# 2_MCU.net
KiCad netlist of a schematic drawn in Altium Designer
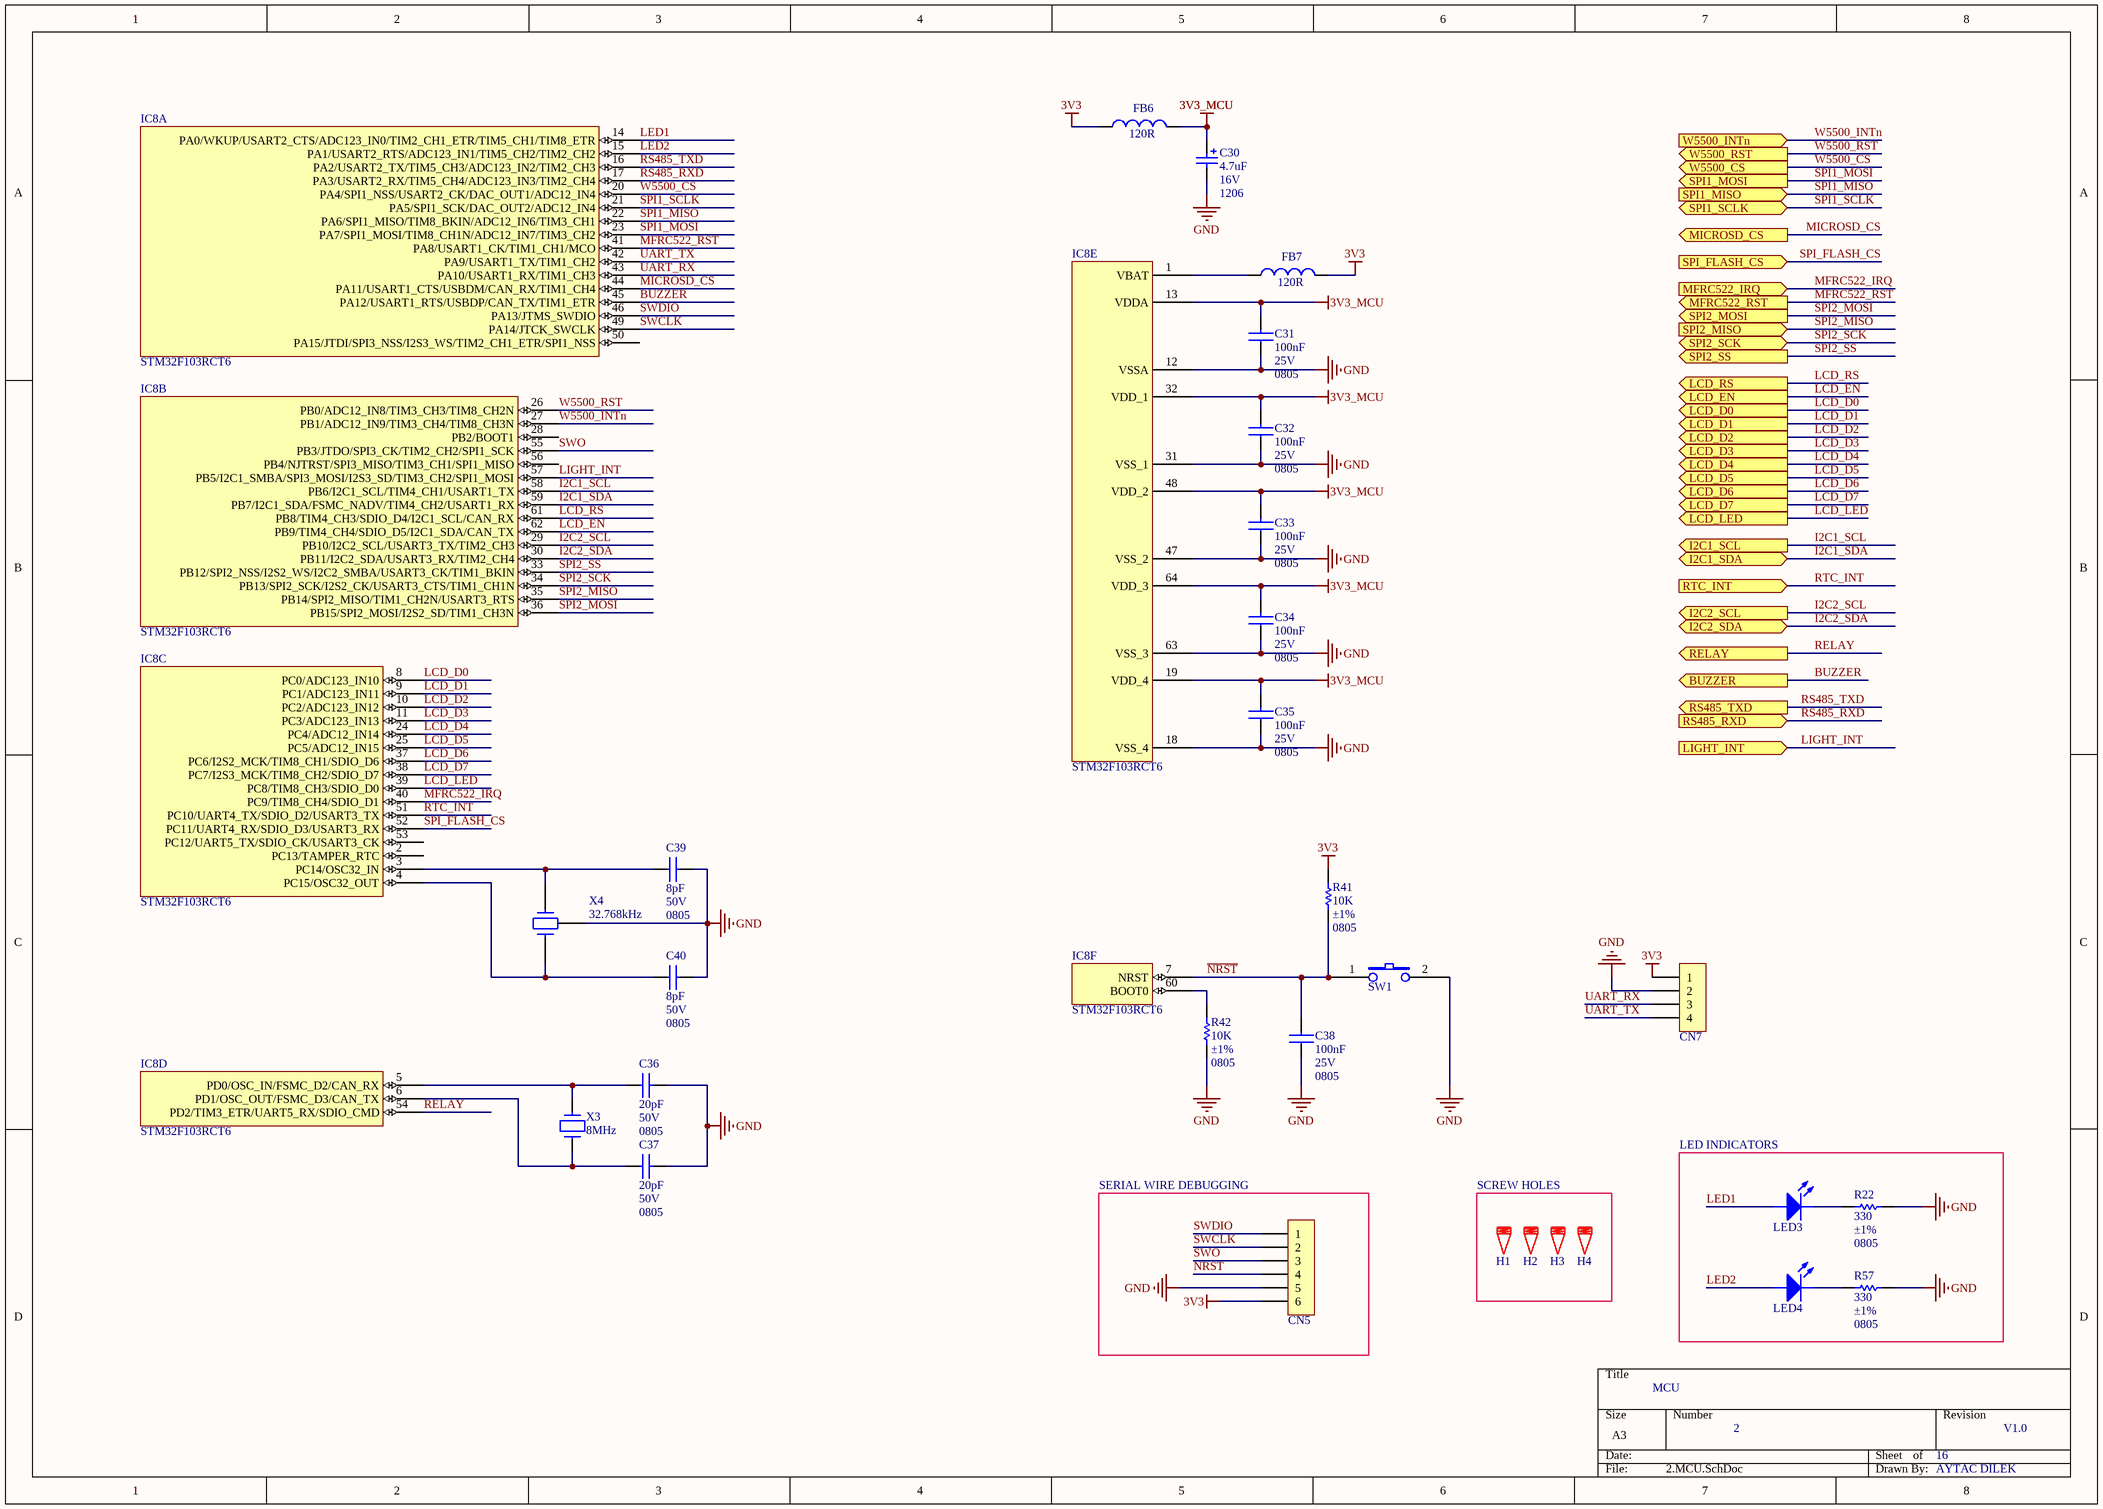
[diagram p0: 2.MCU.SchDoc]

(export (version "E")
  (design (tool "Eeschema 10.0.6"))
  (components
    (comp (ref "C30")
      (value "4.7uF")
      (footprint "CAPMP3216X16N_EIA-1206_CASE-A")
      (description "CAP TANT 4.7UF 16V 10% 1206")
      (fields
        (field (name "PART NUMBER") "SCAP01400003")
        (field (name "TOLERANCE") "±10%")
        (field (name "VOLTAGE - RATED") "16V")
        (field (name "PACKAGE / CASE") "1206")
      )
      (libsource (lib "ComponentDatabase") (part "CAP_P"))
    )
    (comp (ref "C31")
      (value "CAP_NP")
      (footprint "CAPC2012X100N_EIA0805")
      (description "CAP CER 0.1UF 25V X7R 0805")
      (fields
        (field (name "PART NUMBER") "SCAP00300093")
        (field (name "CAPACITANCE") "100nF")
        (field (name "TOLERANCE") "±10%")
        (field (name "VOLTAGE - RATED") "25V")
        (field (name "PACKAGE / CASE") "0805")
      )
      (libsource (lib "ComponentDatabase") (part "CAP_NP"))
    )
    (comp (ref "C32")
      (value "CAP_NP")
      (footprint "CAPC2012X100N_EIA0805")
      (description "CAP CER 0.1UF 25V X7R 0805")
      (fields
        (field (name "PART NUMBER") "SCAP00300093")
        (field (name "CAPACITANCE") "100nF")
        (field (name "TOLERANCE") "±10%")
        (field (name "VOLTAGE - RATED") "25V")
        (field (name "PACKAGE / CASE") "0805")
      )
      (libsource (lib "ComponentDatabase") (part "CAP_NP"))
    )
    (comp (ref "C33")
      (value "CAP_NP")
      (footprint "CAPC2012X100N_EIA0805")
      (description "CAP CER 0.1UF 25V X7R 0805")
      (fields
        (field (name "PART NUMBER") "SCAP00300093")
        (field (name "CAPACITANCE") "100nF")
        (field (name "TOLERANCE") "±10%")
        (field (name "VOLTAGE - RATED") "25V")
        (field (name "PACKAGE / CASE") "0805")
      )
      (libsource (lib "ComponentDatabase") (part "CAP_NP"))
    )
    (comp (ref "C34")
      (value "CAP_NP")
      (footprint "CAPC2012X100N_EIA0805")
      (description "CAP CER 0.1UF 25V X7R 0805")
      (fields
        (field (name "PART NUMBER") "SCAP00300093")
        (field (name "CAPACITANCE") "100nF")
        (field (name "TOLERANCE") "±10%")
        (field (name "VOLTAGE - RATED") "25V")
        (field (name "PACKAGE / CASE") "0805")
      )
      (libsource (lib "ComponentDatabase") (part "CAP_NP"))
    )
    (comp (ref "C35")
      (value "CAP_NP")
      (footprint "CAPC2012X100N_EIA0805")
      (description "CAP CER 0.1UF 25V X7R 0805")
      (fields
        (field (name "PART NUMBER") "SCAP00300093")
        (field (name "CAPACITANCE") "100nF")
        (field (name "TOLERANCE") "±10%")
        (field (name "VOLTAGE - RATED") "25V")
        (field (name "PACKAGE / CASE") "0805")
      )
      (libsource (lib "ComponentDatabase") (part "CAP_NP"))
    )
    (comp (ref "C36")
      (value "CAP_NP")
      (footprint "CAPC2012X100N_EIA0805")
      (description "CAP CER 20PF 50V NP0 0805")
      (fields
        (field (name "PART NUMBER") "SCAP00300041")
        (field (name "CAPACITANCE") "20pF")
        (field (name "TOLERANCE") "±5%")
        (field (name "VOLTAGE - RATED") "50V")
        (field (name "PACKAGE / CASE") "0805")
      )
      (libsource (lib "ComponentDatabase") (part "CAP_NP"))
    )
    (comp (ref "C37")
      (value "CAP_NP")
      (footprint "CAPC2012X100N_EIA0805")
      (description "CAP CER 20PF 50V NP0 0805")
      (fields
        (field (name "PART NUMBER") "SCAP00300041")
        (field (name "CAPACITANCE") "20pF")
        (field (name "TOLERANCE") "±5%")
        (field (name "VOLTAGE - RATED") "50V")
        (field (name "PACKAGE / CASE") "0805")
      )
      (libsource (lib "ComponentDatabase") (part "CAP_NP"))
    )
    (comp (ref "C38")
      (value "CAP_NP")
      (footprint "CAPC2012X100N_EIA0805")
      (description "CAP CER 0.1UF 25V X7R 0805")
      (fields
        (field (name "PART NUMBER") "SCAP00300093")
        (field (name "CAPACITANCE") "100nF")
        (field (name "TOLERANCE") "±10%")
        (field (name "VOLTAGE - RATED") "25V")
        (field (name "PACKAGE / CASE") "0805")
      )
      (libsource (lib "ComponentDatabase") (part "CAP_NP"))
    )
    (comp (ref "C39")
      (value "CAP_NP")
      (footprint "CAPC2012X100N_EIA0805")
      (description "CAP CER 8PF 50V NP0 0805")
      (fields
        (field (name "PART NUMBER") "SCAP00300030")
        (field (name "CAPACITANCE") "8pF")
        (field (name "TOLERANCE") "±0.25pF")
        (field (name "VOLTAGE - RATED") "50V")
        (field (name "PACKAGE / CASE") "0805")
      )
      (libsource (lib "ComponentDatabase") (part "CAP_NP"))
    )
    (comp (ref "C40")
      (value "CAP_NP")
      (footprint "CAPC2012X100N_EIA0805")
      (description "CAP CER 8PF 50V NP0 0805")
      (fields
        (field (name "PART NUMBER") "SCAP00300030")
        (field (name "CAPACITANCE") "8pF")
        (field (name "TOLERANCE") "±0.25pF")
        (field (name "VOLTAGE - RATED") "50V")
        (field (name "PACKAGE / CASE") "0805")
      )
      (libsource (lib "ComponentDatabase") (part "CAP_NP"))
    )
    (comp (ref "CN5")
      (value "HDR_1X6")
      (footprint "HDRFV6W70P254_1X6_1524X254X1118P")
      (description "CONN ARDUINO HEADER .0100\" 6POS")
      (fields (field (name "PART NUMBER") "SCON00124") (field (name "MANUFACTURER") "Sparkfun"))
      (libsource (lib "ComponentDatabase") (part "HDR_1X6"))
    )
    (comp (ref "CN7")
      (value "HDR_1X4")
      (footprint "HDRFV4W70P254_1X4_1016X254X1118P")
      (description "CONN HEADER 4 POS 2.54")
      (fields (field (name "PART NUMBER") "SCON00140") (field (name "MANUFACTURER") "Wurth Electronics Inc"))
      (libsource (lib "ComponentDatabase") (part "HDR_1X4"))
    )
    (comp (ref "FB6")
      (value "BEAD")
      (footprint "FILC2012X100N_EIA0805")
      (description "FERRITE CHIP POWER 120 OHM SMD")
      (fields
        (field (name "PART NUMBER") "SFIL00005")
        (field (name "IMPEDANCE") "120R")
        (field (name "MANUFACTURER") "Laird-Signal Integrity Products")
      )
      (libsource (lib "ComponentDatabase") (part "BEAD"))
    )
    (comp (ref "FB7")
      (value "BEAD")
      (footprint "FILC2012X100N_EIA0805")
      (description "FERRITE CHIP POWER 120 OHM SMD")
      (fields
        (field (name "PART NUMBER") "SFIL00005")
        (field (name "IMPEDANCE") "120R")
        (field (name "MANUFACTURER") "Laird-Signal Integrity Products")
      )
      (libsource (lib "ComponentDatabase") (part "BEAD"))
    )
    (comp (ref "H1")
      (value "HOLES")
      (footprint "HOLE_125MIL")
      (description "Holes")
      (fields (field (name "PART NUMBER") "SMSC00005"))
      (libsource (lib "ComponentDatabase") (part "HOLES"))
    )
    (comp (ref "H2")
      (value "HOLES")
      (footprint "HOLE_125MIL")
      (description "Holes")
      (fields (field (name "PART NUMBER") "SMSC00005"))
      (libsource (lib "ComponentDatabase") (part "HOLES"))
    )
    (comp (ref "H3")
      (value "HOLES")
      (footprint "HOLE_125MIL")
      (description "Holes")
      (fields (field (name "PART NUMBER") "SMSC00005"))
      (libsource (lib "ComponentDatabase") (part "HOLES"))
    )
    (comp (ref "H4")
      (value "HOLES")
      (footprint "HOLE_125MIL")
      (description "Holes")
      (fields (field (name "PART NUMBER") "SMSC00005"))
      (libsource (lib "ComponentDatabase") (part "HOLES"))
    )
    (comp (ref "IC8")
      (value "STM32F103RCT6")
      (footprint "QFP50P1200X1200X160-64N")
      (description "IC MCU 32BIT 256KB FLASH 64LQFP")
      (fields
        (field (name "PART NUMBER") "SIC00045")
        (field (name "MANUFACTURER PART NUMBER") "STM32F103RCT6")
        (field (name "MANUFACTURER") "STMicroelectronics")
      )
      (libsource (lib "ComponentDatabase") (part "STM32F103RCT6"))
    )
    (comp (ref "LED3")
      (value "LED")
      (footprint "LEDC2012X70N_EIA0805_RED")
      (description "LED SUPER RED CLR THIN 0805 SMD")
      (fields (field (name "PART NUMBER") "SOPT00004") (field (name "MANUFACTURER") "Lite-On Inc"))
      (libsource (lib "ComponentDatabase") (part "LED"))
    )
    (comp (ref "LED4")
      (value "LED")
      (footprint "LEDC2012X70N_EIA0805_RED")
      (description "LED SUPER RED CLR THIN 0805 SMD")
      (fields (field (name "PART NUMBER") "SOPT00004") (field (name "MANUFACTURER") "Lite-On Inc"))
      (libsource (lib "ComponentDatabase") (part "LED"))
    )
    (comp (ref "R22")
      (value "RES")
      (footprint "RESC2013X65N_EIA0805")
      (description "RES SMD 330 OHM 1% 1/8W 0805")
      (fields
        (field (name "PART NUMBER") "SRES03010062")
        (field (name "RESISTANCE (OHM)") "330")
        (field (name "TOLERANCE") "±1%")
        (field (name "PACKAGE / CASE") "0805")
        (field (name "MANUFACTURER") "Yageo")
      )
      (libsource (lib "ComponentDatabase") (part "RES"))
    )
    (comp (ref "R41")
      (value "RES")
      (footprint "RESC2013X65N_EIA0805")
      (description "RES SMD 10K OHM 1% 1/8W 0805")
      (fields
        (field (name "PART NUMBER") "SRES03010098")
        (field (name "RESISTANCE (OHM)") "10K")
        (field (name "TOLERANCE") "±1%")
        (field (name "PACKAGE / CASE") "0805")
        (field (name "MANUFACTURER") "Yageo")
      )
      (libsource (lib "ComponentDatabase") (part "RES"))
    )
    (comp (ref "R42")
      (value "RES")
      (footprint "RESC2013X65N_EIA0805")
      (description "RES SMD 10K OHM 1% 1/8W 0805")
      (fields
        (field (name "PART NUMBER") "SRES03010098")
        (field (name "RESISTANCE (OHM)") "10K")
        (field (name "TOLERANCE") "±1%")
        (field (name "PACKAGE / CASE") "0805")
        (field (name "MANUFACTURER") "Yageo")
      )
      (libsource (lib "ComponentDatabase") (part "RES"))
    )
    (comp (ref "R57")
      (value "RES")
      (footprint "RESC2013X65N_EIA0805")
      (description "RES SMD 330 OHM 1% 1/8W 0805")
      (fields
        (field (name "PART NUMBER") "SRES03010062")
        (field (name "RESISTANCE (OHM)") "330")
        (field (name "TOLERANCE") "±1%")
        (field (name "PACKAGE / CASE") "0805")
        (field (name "MANUFACTURER") "Yageo")
      )
      (libsource (lib "ComponentDatabase") (part "RES"))
    )
    (comp (ref "SW1")
      (value "SWITCH_TACTILE_2PIN")
      (footprint "[C&K]RS-282G05A3-SM_RT")
      (description "SWITCH TACTILE SPST-NO 0.05A 12V")
      (fields (field (name "PART NUMBER") "SSWI00022") (field (name "VOLTAGE") "12VDC"))
      (libsource (lib "ComponentDatabase") (part "SWITCH_TACTILE_2PIN"))
    )
    (comp (ref "X3")
      (value "8MHz")
      (footprint "HC-49/US")
      (description "CRYSTAL 8.0000MHZ 20PF T/H")
      (fields (field (name "PART NUMBER") "SCRY00001") (field (name "MANUFACTURER") "CTS-Frequency Controls"))
      (libsource (lib "ComponentDatabase") (part "CRYSTAL"))
    )
    (comp (ref "X4")
      (value "32.768kHz")
      (footprint "32.768_DIP")
      (description "CRYSTAL 32.768KHZ 6PF THRU")
      (fields (field (name "PART NUMBER") "SCRY00009") (field (name "MANUFACTURER") "Seiko Instruments"))
      (libsource (lib "ComponentDatabase") (part "CRYSTAL_32K"))
    )
  )
  (nets
    (net (code "1") (name "/BUZZER") (class "Default")
      (node (ref "IC8") (pin "45") (pinfunction "PA12/USART1_RTS/USBDP/CAN_TX/TIM1_ETR_45") (pintype "bidirectional"))
    )
    (net (code "2") (name "/I2C1_SCL") (class "Default")
      (node (ref "IC8") (pin "58") (pinfunction "PB6/I2C1_SCL/TIM4_CH1/USART1_TX_58") (pintype "bidirectional"))
    )
    (net (code "3") (name "/I2C1_SDA") (class "Default")
      (node (ref "IC8") (pin "59") (pinfunction "PB7/I2C1_SDA/FSMC_NADV/TIM4_CH2/USART1_RX_59") (pintype "bidirectional"))
    )
    (net (code "4") (name "/I2C2_SCL") (class "Default")
      (node (ref "IC8") (pin "29") (pinfunction "PB10/I2C2_SCL/USART3_TX/TIM2_CH3_29") (pintype "bidirectional"))
    )
    (net (code "5") (name "/I2C2_SDA") (class "Default")
      (node (ref "IC8") (pin "30") (pinfunction "PB11/I2C2_SDA/USART3_RX/TIM2_CH4_30") (pintype "bidirectional"))
    )
    (net (code "6") (name "/LCD_D0") (class "Default")
      (node (ref "IC8") (pin "8") (pinfunction "PC0/ADC123_IN10_8") (pintype "bidirectional"))
    )
    (net (code "7") (name "/LCD_D1") (class "Default")
      (node (ref "IC8") (pin "9") (pinfunction "PC1/ADC123_IN11_9") (pintype "bidirectional"))
    )
    (net (code "8") (name "/LCD_D2") (class "Default")
      (node (ref "IC8") (pin "10") (pinfunction "PC2/ADC123_IN12_10") (pintype "bidirectional"))
    )
    (net (code "9") (name "/LCD_D3") (class "Default")
      (node (ref "IC8") (pin "11") (pinfunction "PC3/ADC123_IN13_11") (pintype "bidirectional"))
    )
    (net (code "10") (name "/LCD_D4") (class "Default")
      (node (ref "IC8") (pin "24") (pinfunction "PC4/ADC12_IN14_24") (pintype "bidirectional"))
    )
    (net (code "11") (name "/LCD_D5") (class "Default")
      (node (ref "IC8") (pin "25") (pinfunction "PC5/ADC12_IN15_25") (pintype "bidirectional"))
    )
    (net (code "12") (name "/LCD_D6") (class "Default")
      (node (ref "IC8") (pin "37") (pinfunction "PC6/I2S2_MCK/TIM8_CH1/SDIO_D6_37") (pintype "bidirectional"))
    )
    (net (code "13") (name "/LCD_D7") (class "Default")
      (node (ref "IC8") (pin "38") (pinfunction "PC7/I2S3_MCK/TIM8_CH2/SDIO_D7_38") (pintype "bidirectional"))
    )
    (net (code "14") (name "/LCD_EN") (class "Default")
      (node (ref "IC8") (pin "62") (pinfunction "PB9/TIM4_CH4/SDIO_D5/I2C1_SDA/CAN_TX_62") (pintype "bidirectional"))
    )
    (net (code "15") (name "/LCD_LED") (class "Default")
      (node (ref "IC8") (pin "39") (pinfunction "PC8/TIM8_CH3/SDIO_D0_39") (pintype "bidirectional"))
    )
    (net (code "16") (name "/LCD_RS") (class "Default")
      (node (ref "IC8") (pin "61") (pinfunction "PB8/TIM4_CH3/SDIO_D4/I2C1_SCL/CAN_RX_61") (pintype "bidirectional"))
    )
    (net (code "17") (name "/LED1") (class "Default")
      (node (ref "IC8") (pin "14") (pinfunction "PA0/WKUP/USART2-CTS/ADC123_IN0/TIM2_CH1_ETR/TIM5_CH1/TIM8_ETR_14") (pintype "bidirectional"))
      (node (ref "LED3") (pin "2") (pinfunction "2_2") (pintype "passive"))
    )
    (net (code "18") (name "/LED2") (class "Default")
      (node (ref "IC8") (pin "15") (pinfunction "PA1/USART2_RTS/ADC123_IN1/TIM5_CH2/TIM2_CH2_15") (pintype "bidirectional"))
      (node (ref "LED4") (pin "2") (pinfunction "2_2") (pintype "passive"))
    )
    (net (code "19") (name "/LIGHT_INT") (class "Default")
      (node (ref "IC8") (pin "57") (pinfunction "PB5/I2C1_SMBA/SPI3_MOSI/I2S3_SD/TIM3_CH2/SPI1_MOSI_57") (pintype "bidirectional"))
    )
    (net (code "20") (name "/MFRC522_IRQ") (class "Default")
      (node (ref "IC8") (pin "40") (pinfunction "PC9/TIM8_CH4/SDIO_D1_40") (pintype "bidirectional"))
    )
    (net (code "21") (name "/MFRC522_RST") (class "Default")
      (node (ref "IC8") (pin "41") (pinfunction "PA8/USART1_CK/TIM1_CH1/MCO_41") (pintype "bidirectional"))
    )
    (net (code "22") (name "/MICROSD_CS") (class "Default")
      (node (ref "IC8") (pin "44") (pinfunction "PA11/USART1_CTS/USBDM/CAN_RX/TIM1_CH4_44") (pintype "bidirectional"))
    )
    (net (code "23") (name "/RELAY") (class "Default")
      (node (ref "IC8") (pin "54") (pinfunction "PD2/TIM3_ETR/UART5_RX/SDIO_CMD_54") (pintype "bidirectional"))
    )
    (net (code "24") (name "/RS485_RXD") (class "Default")
      (node (ref "IC8") (pin "17") (pinfunction "PA3/USART2_RX/TIM5_CH4/ADC123_IN3/TIM2_CH4_17") (pintype "bidirectional"))
    )
    (net (code "25") (name "/RS485_TXD") (class "Default")
      (node (ref "IC8") (pin "16") (pinfunction "PA2/USART2_TX/TIM5_CH3/ADC123_IN2/TIM2_CH3_16") (pintype "bidirectional"))
    )
    (net (code "26") (name "/RTC_INT") (class "Default")
      (node (ref "IC8") (pin "51") (pinfunction "PC10/UART4_TX/SDIO_D2/USART3_TX_51") (pintype "bidirectional"))
    )
    (net (code "27") (name "/SPI1_MISO") (class "Default")
      (node (ref "IC8") (pin "22") (pinfunction "PA6/SPI1_MISO/TIM8_BKIN/ADC12_IN6/TIM3_CH1_22") (pintype "bidirectional"))
    )
    (net (code "28") (name "/SPI1_MOSI") (class "Default")
      (node (ref "IC8") (pin "23") (pinfunction "PA7/SPI1_MOSI/TIM8_CH1N/ADC12_IN7/TIM3_CH2_23") (pintype "bidirectional"))
    )
    (net (code "29") (name "/SPI1_SCLK") (class "Default")
      (node (ref "IC8") (pin "21") (pinfunction "PA5/SPI1_SCK/DAC_OUT2/ADC12_IN4_21") (pintype "bidirectional"))
    )
    (net (code "30") (name "/SPI2_MISO") (class "Default")
      (node (ref "IC8") (pin "35") (pinfunction "PB14/SPI2_MISO/TIM1_CH2N/USART3_RTS_35") (pintype "bidirectional"))
    )
    (net (code "31") (name "/SPI2_MOSI") (class "Default")
      (node (ref "IC8") (pin "36") (pinfunction "PB15/SPI2_MOSI/I2S2_SD/TIM1_CH3N_36") (pintype "bidirectional"))
    )
    (net (code "32") (name "/SPI2_SCK") (class "Default")
      (node (ref "IC8") (pin "34") (pinfunction "PB13/SPI2_SCK/I2S2_CK/USART3_CTS/TIM1_CH1N_34") (pintype "bidirectional"))
    )
    (net (code "33") (name "/SPI2_SS") (class "Default")
      (node (ref "IC8") (pin "33") (pinfunction "PB12/SPI2_NSS/I2S2_WS/I2C2_SMBA/USART3_CK/TIM1_BKIN_33") (pintype "bidirectional"))
    )
    (net (code "34") (name "/SPI_FLASH_CS") (class "Default")
      (node (ref "IC8") (pin "52") (pinfunction "PC11/UART4_RX/SDIO_D3/USART3_RX_52") (pintype "bidirectional"))
    )
    (net (code "35") (name "/SWCLK") (class "Default")
      (node (ref "CN5") (pin "2") (pinfunction "2_2") (pintype "passive"))
      (node (ref "IC8") (pin "49") (pinfunction "PA14/JTCK_SWCLK_49") (pintype "bidirectional"))
    )
    (net (code "36") (name "/SWDIO") (class "Default")
      (node (ref "CN5") (pin "1") (pinfunction "1_1") (pintype "passive"))
      (node (ref "IC8") (pin "46") (pinfunction "PA13/JTMS_SWDIO_46") (pintype "bidirectional"))
    )
    (net (code "37") (name "/SWO") (class "Default")
      (node (ref "CN5") (pin "3") (pinfunction "3_3") (pintype "passive"))
      (node (ref "IC8") (pin "55") (pinfunction "PB3/JTDO/SPI3_CK/TIM2_CH2/SPI1_SCK_55") (pintype "bidirectional"))
    )
    (net (code "38") (name "/UART_RX") (class "Default")
      (node (ref "CN7") (pin "3") (pinfunction "3_3") (pintype "passive"))
      (node (ref "IC8") (pin "43") (pinfunction "PA10/USART1_RX/TIM1_CH3_43") (pintype "bidirectional"))
    )
    (net (code "39") (name "/UART_TX") (class "Default")
      (node (ref "CN7") (pin "4") (pinfunction "4_4") (pintype "passive"))
      (node (ref "IC8") (pin "42") (pinfunction "PA9/USART1_TX/TIM1_CH2_42") (pintype "bidirectional"))
    )
    (net (code "40") (name "/W5500_CS") (class "Default")
      (node (ref "IC8") (pin "20") (pinfunction "PA4/SPI1_NSS/USART2_CK/DAC_OUT1/ADC12_IN4_20") (pintype "bidirectional"))
    )
    (net (code "41") (name "/W5500_INTn") (class "Default")
      (node (ref "IC8") (pin "27") (pinfunction "PB1/ADC12_IN9/TIM3_CH4/TIM8_CH3N_27") (pintype "bidirectional"))
    )
    (net (code "42") (name "/W5500_RST") (class "Default")
      (node (ref "IC8") (pin "26") (pinfunction "PB0/ADC12_IN8/TIM3_CH3/TIM8_CH2N_26") (pintype "bidirectional"))
    )
    (net (code "43") (name "/~{NRST}") (class "Default")
      (node (ref "C38") (pin "2") (pinfunction "2_2") (pintype "passive"))
      (node (ref "CN5") (pin "4") (pinfunction "4_4") (pintype "passive"))
      (node (ref "IC8") (pin "7") (pinfunction "NRST_7") (pintype "bidirectional"))
      (node (ref "R41") (pin "2") (pinfunction "2_2") (pintype "passive"))
      (node (ref "SW1") (pin "1") (pinfunction "A0_1") (pintype "passive"))
    )
    (net (code "44") (name "3V3") (class "Default")
      (node (ref "CN5") (pin "6") (pinfunction "6_6") (pintype "passive"))
      (node (ref "CN7") (pin "1") (pinfunction "1_1") (pintype "passive"))
      (node (ref "FB6") (pin "1") (pinfunction "1_1") (pintype "passive"))
      (node (ref "FB7") (pin "2") (pinfunction "2_2") (pintype "passive"))
      (node (ref "R41") (pin "1") (pinfunction "1_1") (pintype "passive"))
    )
    (net (code "45") (name "3V3_MCU") (class "Default")
      (node (ref "C30") (pin "1") (pinfunction "1_1") (pintype "passive"))
      (node (ref "C31") (pin "2") (pinfunction "2_2") (pintype "passive"))
      (node (ref "C32") (pin "2") (pinfunction "2_2") (pintype "passive"))
      (node (ref "C33") (pin "2") (pinfunction "2_2") (pintype "passive"))
      (node (ref "C34") (pin "2") (pinfunction "2_2") (pintype "passive"))
      (node (ref "C35") (pin "2") (pinfunction "2_2") (pintype "passive"))
      (node (ref "FB6") (pin "2") (pinfunction "2_2") (pintype "passive"))
      (node (ref "IC8") (pin "13") (pinfunction "VDDA_13") (pintype "power_in"))
      (node (ref "IC8") (pin "19") (pinfunction "VDD_4_19") (pintype "power_in"))
      (node (ref "IC8") (pin "32") (pinfunction "VDD_1_32") (pintype "power_in"))
      (node (ref "IC8") (pin "48") (pinfunction "VDD_2_48") (pintype "power_in"))
      (node (ref "IC8") (pin "64") (pinfunction "VDD_3_64") (pintype "power_in"))
    )
    (net (code "46") (name "GND") (class "Default")
      (node (ref "C30") (pin "2") (pinfunction "2_2") (pintype "passive"))
      (node (ref "C31") (pin "1") (pinfunction "1_1") (pintype "passive"))
      (node (ref "C32") (pin "1") (pinfunction "1_1") (pintype "passive"))
      (node (ref "C33") (pin "1") (pinfunction "1_1") (pintype "passive"))
      (node (ref "C34") (pin "1") (pinfunction "1_1") (pintype "passive"))
      (node (ref "C35") (pin "1") (pinfunction "1_1") (pintype "passive"))
      (node (ref "C36") (pin "2") (pinfunction "2_2") (pintype "passive"))
      (node (ref "C37") (pin "2") (pinfunction "2_2") (pintype "passive"))
      (node (ref "C38") (pin "1") (pinfunction "1_1") (pintype "passive"))
      (node (ref "C39") (pin "2") (pinfunction "2_2") (pintype "passive"))
      (node (ref "C40") (pin "2") (pinfunction "2_2") (pintype "passive"))
      (node (ref "CN5") (pin "5") (pinfunction "5_5") (pintype "passive"))
      (node (ref "CN7") (pin "2") (pinfunction "2_2") (pintype "passive"))
      (node (ref "IC8") (pin "12") (pinfunction "VSSA_12") (pintype "power_in"))
      (node (ref "IC8") (pin "18") (pinfunction "VSS_4_18") (pintype "power_in"))
      (node (ref "IC8") (pin "31") (pinfunction "VSS_1_31") (pintype "power_in"))
      (node (ref "IC8") (pin "47") (pinfunction "VSS_2_47") (pintype "power_in"))
      (node (ref "IC8") (pin "63") (pinfunction "VSS_3_63") (pintype "power_in"))
      (node (ref "R22") (pin "2") (pinfunction "2_2") (pintype "passive"))
      (node (ref "R42") (pin "2") (pinfunction "2_2") (pintype "passive"))
      (node (ref "R57") (pin "2") (pinfunction "2_2") (pintype "passive"))
      (node (ref "SW1") (pin "2") (pinfunction "A1_2") (pintype "passive"))
      (node (ref "X4") (pin "3") (pinfunction "3_3") (pintype "power_in"))
    )
    (net (code "47") (name "Net-(IC8C-PC14{slash}OSC32_IN)") (class "Default")
      (node (ref "C39") (pin "1") (pinfunction "1_1") (pintype "passive"))
      (node (ref "IC8") (pin "3") (pinfunction "PC14/OSC32_IN_3") (pintype "bidirectional"))
      (node (ref "X4") (pin "2") (pinfunction "2_2") (pintype "passive"))
    )
    (net (code "48") (name "Net-(IC8C-PC15{slash}OSC32_OUT)") (class "Default")
      (node (ref "C40") (pin "1") (pinfunction "1_1") (pintype "passive"))
      (node (ref "IC8") (pin "4") (pinfunction "PC15/OSC32_OUT_4") (pintype "bidirectional"))
      (node (ref "X4") (pin "1") (pinfunction "1_1") (pintype "passive"))
    )
    (net (code "49") (name "Net-(IC8D-PD0{slash}OSC_IN{slash}FSMC_D2{slash}CAN_RX)") (class "Default")
      (node (ref "C36") (pin "1") (pinfunction "1_1") (pintype "passive"))
      (node (ref "IC8") (pin "5") (pinfunction "PD0/OSC_IN/FSMC_D2/CAN_RX_5") (pintype "bidirectional"))
      (node (ref "X3") (pin "1") (pinfunction "1_1") (pintype "passive"))
    )
    (net (code "50") (name "Net-(IC8D-PD1{slash}OSC_OUT{slash}FSMC_D3{slash}CAN_TX)") (class "Default")
      (node (ref "C37") (pin "1") (pinfunction "1_1") (pintype "passive"))
      (node (ref "IC8") (pin "6") (pinfunction "PD1/OSC_OUT/FSMC_D3/CAN_TX_6") (pintype "bidirectional"))
      (node (ref "X3") (pin "2") (pinfunction "2_2") (pintype "passive"))
    )
    (net (code "51") (name "Net-(IC8E-VBAT)") (class "Default")
      (node (ref "FB7") (pin "1") (pinfunction "1_1") (pintype "passive"))
      (node (ref "IC8") (pin "1") (pinfunction "VBAT_1") (pintype "power_in"))
    )
    (net (code "52") (name "Net-(IC8F-BOOT0)") (class "Default")
      (node (ref "IC8") (pin "60") (pinfunction "BOOT0_60") (pintype "bidirectional"))
      (node (ref "R42") (pin "1") (pinfunction "1_1") (pintype "passive"))
    )
    (net (code "53") (name "Net-(LED3-Pad1)") (class "Default")
      (node (ref "LED3") (pin "1") (pinfunction "1_1") (pintype "passive"))
      (node (ref "R22") (pin "1") (pinfunction "1_1") (pintype "passive"))
    )
    (net (code "54") (name "Net-(LED4-Pad1)") (class "Default")
      (node (ref "LED4") (pin "1") (pinfunction "1_1") (pintype "passive"))
      (node (ref "R57") (pin "1") (pinfunction "1_1") (pintype "passive"))
    )
    (net (code "55") (name "unconnected-(IC8A-PA15{slash}JTDI{slash}SPI3_NSS{slash}I2S3_WS{slash}TIM2_CH1_ETR{slash}SPI1_NSS-Pad50)") (class "Default")
      (node (ref "IC8") (pin "50") (pinfunction "PA15/JTDI/SPI3_NSS/I2S3_WS/TIM2_CH1_ETR/SPI1_NSS_50") (pintype "bidirectional"))
    )
    (net (code "56") (name "unconnected-(IC8B-PB2{slash}BOOT1-Pad28)") (class "Default")
      (node (ref "IC8") (pin "28") (pinfunction "PB2/BOOT1_28") (pintype "bidirectional"))
    )
    (net (code "57") (name "unconnected-(IC8B-PB4{slash}NJTRST{slash}SPI3_MISO{slash}TIM3_CH1{slash}SPI1_MISO-Pad56)") (class "Default")
      (node (ref "IC8") (pin "56") (pinfunction "PB4/NJTRST/SPI3_MISO/TIM3_CH1/SPI1_MISO_56") (pintype "bidirectional"))
    )
    (net (code "58") (name "unconnected-(IC8C-PC12{slash}UART5_TX{slash}SDIO_CK{slash}USART3_CK-Pad53)") (class "Default")
      (node (ref "IC8") (pin "53") (pinfunction "PC12/UART5_TX/SDIO_CK/USART3_CK_53") (pintype "bidirectional"))
    )
    (net (code "59") (name "unconnected-(IC8C-PC13{slash}TAMPER_RTC-Pad2)") (class "Default")
      (node (ref "IC8") (pin "2") (pinfunction "PC13/TAMPER_RTC_2") (pintype "bidirectional"))
    )
  )
)
